# 16f1619_nokia.net
KiCad netlist of a schematic drawn in EAGLE
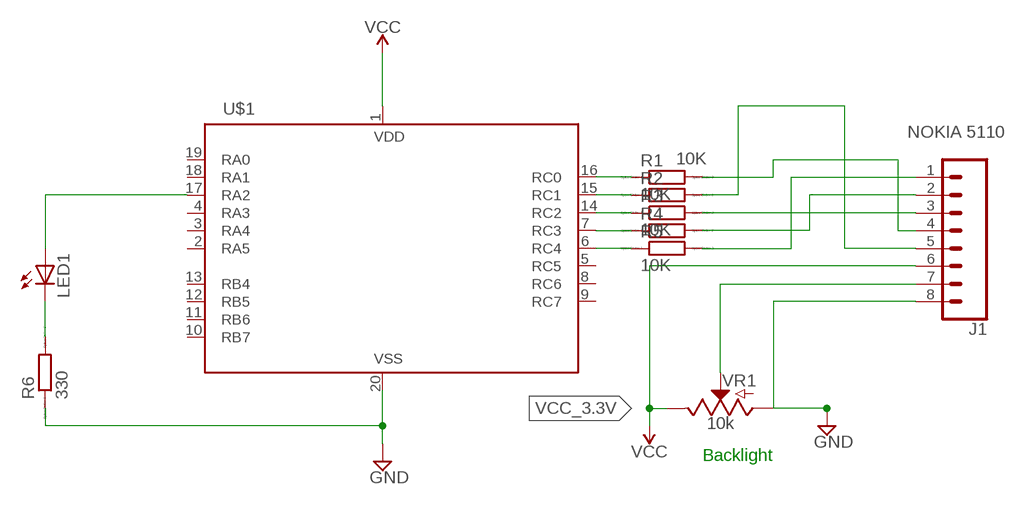
[diagram p0: schematic, sheet 1]

(export (version "E")
  (design (tool "Eeschema 10.0.6"))
  (components
    (comp (ref "J1")
      (value "NOKIA 5110")
      (footprint "eagle-import:1X08_FEMALE_LOCK")
      (libsource (lib "eagle-import") (part "CONN_08FEMALE_LOCK"))
    )
    (comp (ref "LED1")
      (value "LEDB153")
      (footprint "eagle-import:Q62902-B153")
      (libsource (lib "eagle-import") (part "LEDB153"))
    )
    (comp (ref "R1")
      (value "10K")
      (footprint "eagle-import:R3216")
      (libsource (lib "eagle-import") (part "RR3216"))
    )
    (comp (ref "R2")
      (value "10K")
      (footprint "eagle-import:R3216")
      (libsource (lib "eagle-import") (part "RR3216"))
    )
    (comp (ref "R3")
      (value "10K")
      (footprint "eagle-import:R3216")
      (libsource (lib "eagle-import") (part "RR3216"))
    )
    (comp (ref "R4")
      (value "RR3216")
      (footprint "eagle-import:R3216")
      (libsource (lib "eagle-import") (part "RR3216"))
    )
    (comp (ref "R5")
      (value "10K")
      (footprint "eagle-import:R3216")
      (libsource (lib "eagle-import") (part "RR3216"))
    )
    (comp (ref "R6")
      (value "330")
      (footprint "eagle-import:R3216")
      (libsource (lib "eagle-import") (part "RR3216"))
    )
    (comp (ref "U$1")
      (value "PIC16F1619-DIP")
      (footprint "eagle-import:DIP20B")
      (libsource (lib "eagle-import") (part "PIC16F1619-DIP"))
    )
    (comp (ref "VR1")
      (value "10k")
      (footprint "eagle-import:POT-PTH-ALPS")
      (libsource (lib "eagle-import") (part "POTENTIOMETER-PTH-9MM-1/20W-20%"))
    )
  )
  (nets
    (net (code "1") (name "GND") (class "Default")
      (node (ref "J1") (pin "8") (pinfunction "8_8") (pintype "passive"))
      (node (ref "R6") (pin "1") (pinfunction "1_1") (pintype "passive"))
      (node (ref "U$1") (pin "20") (pinfunction "VSS_20") (pintype "power_in"))
      (node (ref "VR1") (pin "P$3") (pinfunction "A_P$3") (pintype "passive"))
    )
    (net (code "2") (name "Net-(J1-Pad1)") (class "Default")
      (node (ref "J1") (pin "1") (pinfunction "1_1") (pintype "passive"))
      (node (ref "R5") (pin "2") (pinfunction "2_2") (pintype "passive"))
    )
    (net (code "3") (name "Net-(J1-Pad2)") (class "Default")
      (node (ref "J1") (pin "2") (pinfunction "2_2") (pintype "passive"))
      (node (ref "R4") (pin "2") (pinfunction "2_2") (pintype "passive"))
    )
    (net (code "4") (name "Net-(J1-Pad3)") (class "Default")
      (node (ref "J1") (pin "3") (pinfunction "3_3") (pintype "passive"))
      (node (ref "R3") (pin "2") (pinfunction "2_2") (pintype "passive"))
    )
    (net (code "5") (name "Net-(J1-Pad4)") (class "Default")
      (node (ref "J1") (pin "4") (pinfunction "4_4") (pintype "passive"))
      (node (ref "R1") (pin "2") (pinfunction "2_2") (pintype "passive"))
    )
    (net (code "6") (name "Net-(J1-Pad5)") (class "Default")
      (node (ref "J1") (pin "5") (pinfunction "5_5") (pintype "passive"))
      (node (ref "R2") (pin "2") (pinfunction "2_2") (pintype "passive"))
    )
    (net (code "7") (name "Net-(LED1-C)") (class "Default")
      (node (ref "LED1") (pin "K") (pinfunction "C_K") (pintype "passive"))
      (node (ref "R6") (pin "2") (pinfunction "2_2") (pintype "passive"))
    )
    (net (code "8") (name "Net-(U$1-RA2)") (class "Default")
      (node (ref "LED1") (pin "A") (pinfunction "A_A") (pintype "passive"))
      (node (ref "U$1") (pin "17") (pinfunction "RA2_17") (pintype "bidirectional"))
    )
    (net (code "9") (name "Net-(U$1-RC0)") (class "Default")
      (node (ref "R1") (pin "1") (pinfunction "1_1") (pintype "passive"))
      (node (ref "U$1") (pin "16") (pinfunction "RC0_16") (pintype "bidirectional"))
    )
    (net (code "10") (name "Net-(U$1-RC1)") (class "Default")
      (node (ref "R2") (pin "1") (pinfunction "1_1") (pintype "passive"))
      (node (ref "U$1") (pin "15") (pinfunction "RC1_15") (pintype "bidirectional"))
    )
    (net (code "11") (name "Net-(U$1-RC2)") (class "Default")
      (node (ref "R3") (pin "1") (pinfunction "1_1") (pintype "passive"))
      (node (ref "U$1") (pin "14") (pinfunction "RC2_14") (pintype "bidirectional"))
    )
    (net (code "12") (name "Net-(U$1-RC3)") (class "Default")
      (node (ref "R4") (pin "1") (pinfunction "1_1") (pintype "passive"))
      (node (ref "U$1") (pin "7") (pinfunction "RC3_7") (pintype "bidirectional"))
    )
    (net (code "13") (name "Net-(U$1-RC4)") (class "Default")
      (node (ref "R5") (pin "1") (pinfunction "1_1") (pintype "passive"))
      (node (ref "U$1") (pin "6") (pinfunction "RC4_6") (pintype "bidirectional"))
    )
    (net (code "14") (name "Net-(VR1-S)") (class "Default")
      (node (ref "J1") (pin "7") (pinfunction "7_7") (pintype "passive"))
      (node (ref "VR1") (pin "P$2") (pinfunction "S_P$2") (pintype "passive"))
    )
    (net (code "15") (name "VCC_3.3V") (class "Default")
      (node (ref "J1") (pin "6") (pinfunction "6_6") (pintype "passive"))
      (node (ref "U$1") (pin "1") (pinfunction "VDD_1") (pintype "power_in"))
      (node (ref "VR1") (pin "P$1") (pinfunction "E_P$1") (pintype "passive"))
    )
    (net (code "16") (name "unconnected-(U$1-RA0-Pad19)") (class "Default")
      (node (ref "U$1") (pin "19") (pinfunction "RA0_19") (pintype "bidirectional"))
    )
    (net (code "17") (name "unconnected-(U$1-RA1-Pad18)") (class "Default")
      (node (ref "U$1") (pin "18") (pinfunction "RA1_18") (pintype "bidirectional"))
    )
    (net (code "18") (name "unconnected-(U$1-RA3-Pad4)") (class "Default")
      (node (ref "U$1") (pin "4") (pinfunction "RA3_4") (pintype "input"))
    )
    (net (code "19") (name "unconnected-(U$1-RA4-Pad3)") (class "Default")
      (node (ref "U$1") (pin "3") (pinfunction "RA4_3") (pintype "bidirectional"))
    )
    (net (code "20") (name "unconnected-(U$1-RA5-Pad2)") (class "Default")
      (node (ref "U$1") (pin "2") (pinfunction "RA5_2") (pintype "bidirectional"))
    )
    (net (code "21") (name "unconnected-(U$1-RB4-Pad13)") (class "Default")
      (node (ref "U$1") (pin "13") (pinfunction "RB4_13") (pintype "bidirectional"))
    )
    (net (code "22") (name "unconnected-(U$1-RB5-Pad12)") (class "Default")
      (node (ref "U$1") (pin "12") (pinfunction "RB5_12") (pintype "bidirectional"))
    )
    (net (code "23") (name "unconnected-(U$1-RB6-Pad11)") (class "Default")
      (node (ref "U$1") (pin "11") (pinfunction "RB6_11") (pintype "bidirectional"))
    )
    (net (code "24") (name "unconnected-(U$1-RB7-Pad10)") (class "Default")
      (node (ref "U$1") (pin "10") (pinfunction "RB7_10") (pintype "bidirectional"))
    )
    (net (code "25") (name "unconnected-(U$1-RC5-Pad5)") (class "Default")
      (node (ref "U$1") (pin "5") (pinfunction "RC5_5") (pintype "bidirectional"))
    )
    (net (code "26") (name "unconnected-(U$1-RC6-Pad8)") (class "Default")
      (node (ref "U$1") (pin "8") (pinfunction "RC6_8") (pintype "bidirectional"))
    )
    (net (code "27") (name "unconnected-(U$1-RC7-Pad9)") (class "Default")
      (node (ref "U$1") (pin "9") (pinfunction "RC7_9") (pintype "bidirectional"))
    )
  )
)
